# M228A.net
KiCad netlist of a schematic drawn in EAGLE
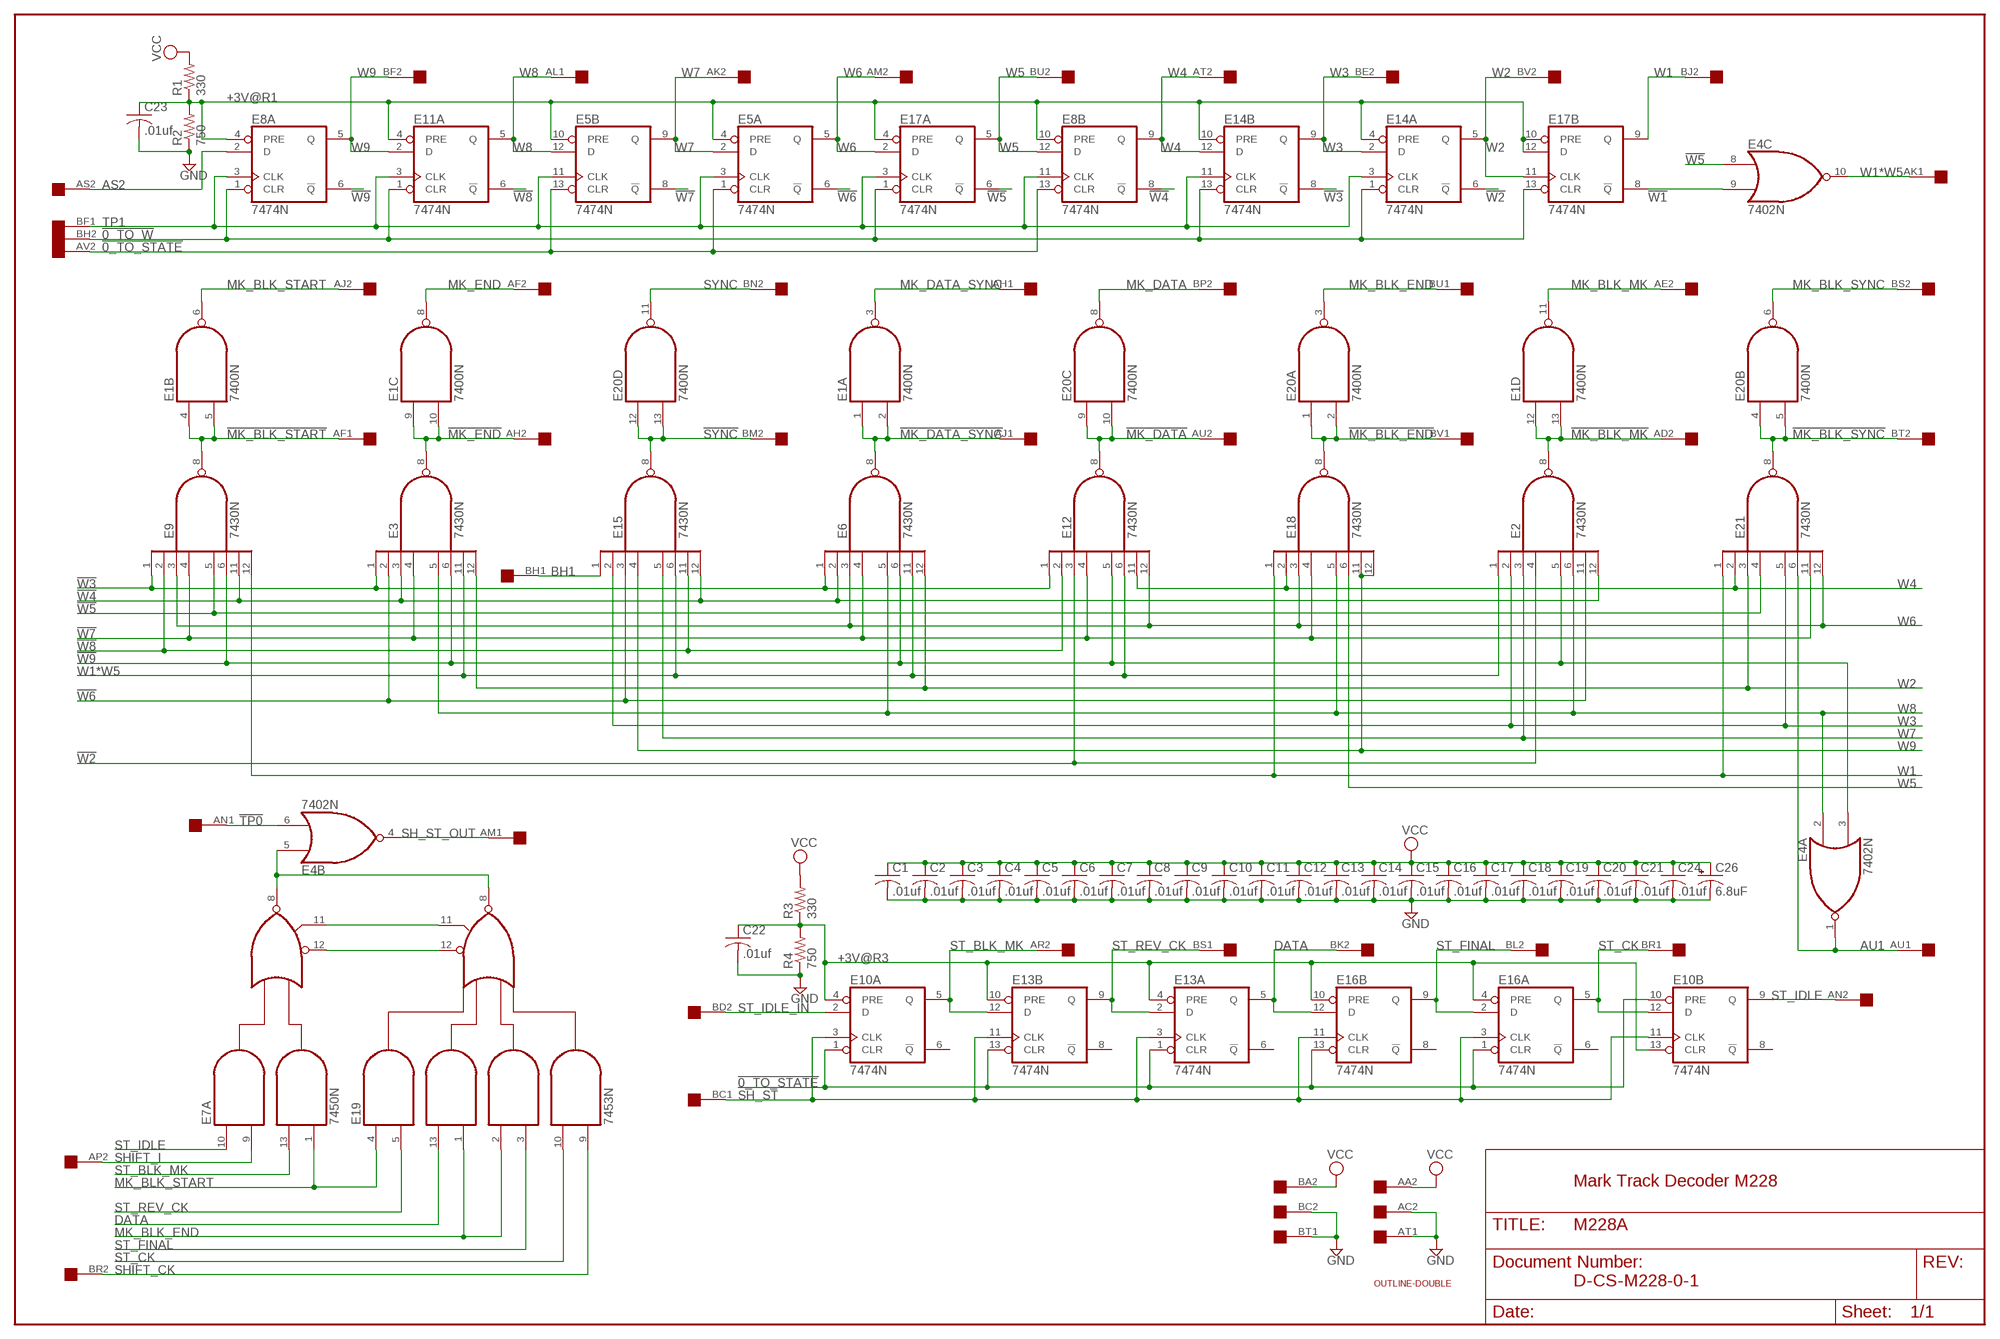
[diagram p0: schematic, sheet 1]

(export (version "E")
  (design (tool "Eeschema 10.0.6"))
  (components
    (comp (ref "C1")
      (value ".01uf")
      (footprint "eagle-import:C050-025X075")
      (libsource (lib "eagle-import") (part "C-US050-025X075"))
    )
    (comp (ref "C2")
      (value ".01uf")
      (footprint "eagle-import:C050-025X075")
      (libsource (lib "eagle-import") (part "C-US050-025X075"))
    )
    (comp (ref "C3")
      (value ".01uf")
      (footprint "eagle-import:C050-025X075")
      (libsource (lib "eagle-import") (part "C-US050-025X075"))
    )
    (comp (ref "C4")
      (value ".01uf")
      (footprint "eagle-import:C050-025X075")
      (libsource (lib "eagle-import") (part "C-US050-025X075"))
    )
    (comp (ref "C5")
      (value ".01uf")
      (footprint "eagle-import:C050-025X075")
      (libsource (lib "eagle-import") (part "C-US050-025X075"))
    )
    (comp (ref "C6")
      (value ".01uf")
      (footprint "eagle-import:C050-025X075")
      (libsource (lib "eagle-import") (part "C-US050-025X075"))
    )
    (comp (ref "C7")
      (value ".01uf")
      (footprint "eagle-import:C050-025X075")
      (libsource (lib "eagle-import") (part "C-US050-025X075"))
    )
    (comp (ref "C8")
      (value ".01uf")
      (footprint "eagle-import:C050-025X075")
      (libsource (lib "eagle-import") (part "C-US050-025X075"))
    )
    (comp (ref "C9")
      (value ".01uf")
      (footprint "eagle-import:C050-025X075")
      (libsource (lib "eagle-import") (part "C-US050-025X075"))
    )
    (comp (ref "C10")
      (value ".01uf")
      (footprint "eagle-import:C050-025X075")
      (libsource (lib "eagle-import") (part "C-US050-025X075"))
    )
    (comp (ref "C11")
      (value ".01uf")
      (footprint "eagle-import:C050-025X075")
      (libsource (lib "eagle-import") (part "C-US050-025X075"))
    )
    (comp (ref "C12")
      (value ".01uf")
      (footprint "eagle-import:C050-025X075")
      (libsource (lib "eagle-import") (part "C-US050-025X075"))
    )
    (comp (ref "C13")
      (value ".01uf")
      (footprint "eagle-import:C050-025X075")
      (libsource (lib "eagle-import") (part "C-US050-025X075"))
    )
    (comp (ref "C14")
      (value ".01uf")
      (footprint "eagle-import:C050-025X075")
      (libsource (lib "eagle-import") (part "C-US050-025X075"))
    )
    (comp (ref "C15")
      (value ".01uf")
      (footprint "eagle-import:C050-025X075")
      (libsource (lib "eagle-import") (part "C-US050-025X075"))
    )
    (comp (ref "C16")
      (value ".01uf")
      (footprint "eagle-import:C050-025X075")
      (libsource (lib "eagle-import") (part "C-US050-025X075"))
    )
    (comp (ref "C17")
      (value ".01uf")
      (footprint "eagle-import:C050-025X075")
      (libsource (lib "eagle-import") (part "C-US050-025X075"))
    )
    (comp (ref "C18")
      (value ".01uf")
      (footprint "eagle-import:C050-025X075")
      (libsource (lib "eagle-import") (part "C-US050-025X075"))
    )
    (comp (ref "C19")
      (value ".01uf")
      (footprint "eagle-import:C050-025X075")
      (libsource (lib "eagle-import") (part "C-US050-025X075"))
    )
    (comp (ref "C20")
      (value ".01uf")
      (footprint "eagle-import:C050-025X075")
      (libsource (lib "eagle-import") (part "C-US050-025X075"))
    )
    (comp (ref "C21")
      (value ".01uf")
      (footprint "eagle-import:C050-025X075")
      (libsource (lib "eagle-import") (part "C-US050-025X075"))
    )
    (comp (ref "C22")
      (value ".01uf")
      (footprint "eagle-import:C050-025X075")
      (libsource (lib "eagle-import") (part "C-US050-025X075"))
    )
    (comp (ref "C23")
      (value ".01uf")
      (footprint "eagle-import:C050-025X075")
      (libsource (lib "eagle-import") (part "C-US050-025X075"))
    )
    (comp (ref "C24")
      (value ".01uf")
      (footprint "eagle-import:C050-025X075")
      (libsource (lib "eagle-import") (part "C-US050-025X075"))
    )
    (comp (ref "C26")
      (value "6.8uF")
      (footprint "eagle-import:E22-6")
      (libsource (lib "eagle-import") (part "CPOL-USE22-6AXIAL"))
    )
    (comp (ref "E1")
      (value "7400N")
      (footprint "eagle-import:DIL14")
      (libsource (lib "eagle-import") (part "7400N"))
    )
    (comp (ref "E2")
      (value "7430N")
      (footprint "eagle-import:DIL14")
      (libsource (lib "eagle-import") (part "7430N"))
    )
    (comp (ref "E3")
      (value "7430N")
      (footprint "eagle-import:DIL14")
      (libsource (lib "eagle-import") (part "7430N"))
    )
    (comp (ref "E4")
      (value "7402N")
      (footprint "eagle-import:DIL14")
      (libsource (lib "eagle-import") (part "7402N"))
    )
    (comp (ref "E5")
      (value "7474N")
      (footprint "eagle-import:DIL14")
      (libsource (lib "eagle-import") (part "7474NS"))
    )
    (comp (ref "E6")
      (value "7430N")
      (footprint "eagle-import:DIL14")
      (libsource (lib "eagle-import") (part "7430N"))
    )
    (comp (ref "E7")
      (value "7450N")
      (footprint "eagle-import:DIL14")
      (libsource (lib "eagle-import") (part "7450N"))
    )
    (comp (ref "E8")
      (value "7474N")
      (footprint "eagle-import:DIL14")
      (libsource (lib "eagle-import") (part "7474NS"))
    )
    (comp (ref "E9")
      (value "7430N")
      (footprint "eagle-import:DIL14")
      (libsource (lib "eagle-import") (part "7430N"))
    )
    (comp (ref "E10")
      (value "7474N")
      (footprint "eagle-import:DIL14")
      (libsource (lib "eagle-import") (part "7474NS"))
    )
    (comp (ref "E11")
      (value "7474N")
      (footprint "eagle-import:DIL14")
      (libsource (lib "eagle-import") (part "7474NS"))
    )
    (comp (ref "E12")
      (value "7430N")
      (footprint "eagle-import:DIL14")
      (libsource (lib "eagle-import") (part "7430N"))
    )
    (comp (ref "E13")
      (value "7474N")
      (footprint "eagle-import:DIL14")
      (libsource (lib "eagle-import") (part "7474NS"))
    )
    (comp (ref "E14")
      (value "7474N")
      (footprint "eagle-import:DIL14")
      (libsource (lib "eagle-import") (part "7474NS"))
    )
    (comp (ref "E15")
      (value "7430N")
      (footprint "eagle-import:DIL14")
      (libsource (lib "eagle-import") (part "7430N"))
    )
    (comp (ref "E16")
      (value "7474N")
      (footprint "eagle-import:DIL14")
      (libsource (lib "eagle-import") (part "7474NS"))
    )
    (comp (ref "E17")
      (value "7474N")
      (footprint "eagle-import:DIL14")
      (libsource (lib "eagle-import") (part "7474NS"))
    )
    (comp (ref "E18")
      (value "7430N")
      (footprint "eagle-import:DIL14")
      (libsource (lib "eagle-import") (part "7430N"))
    )
    (comp (ref "E19")
      (value "7453N")
      (footprint "eagle-import:DIL14")
      (libsource (lib "eagle-import") (part "7453N"))
    )
    (comp (ref "E20")
      (value "7400N")
      (footprint "eagle-import:DIL14")
      (libsource (lib "eagle-import") (part "7400N"))
    )
    (comp (ref "E21")
      (value "7430N")
      (footprint "eagle-import:DIL14")
      (libsource (lib "eagle-import") (part "7430N"))
    )
    (comp (ref "R1")
      (value "330")
      (footprint "eagle-import:0207_10")
      (libsource (lib "eagle-import") (part "R-US_0207/10"))
    )
    (comp (ref "R2")
      (value "750")
      (footprint "eagle-import:0207_10")
      (libsource (lib "eagle-import") (part "R-US_0207/10"))
    )
    (comp (ref "R3")
      (value "330")
      (footprint "eagle-import:0207_10")
      (libsource (lib "eagle-import") (part "R-US_0207/10"))
    )
    (comp (ref "R4")
      (value "750")
      (footprint "eagle-import:0207_10")
      (libsource (lib "eagle-import") (part "R-US_0207/10"))
    )
    (comp (ref "U$1")
      (value "OUTLINE-DOUBLE")
      (footprint "eagle-import:DOUBLE")
      (libsource (lib "eagle-import") (part "OUTLINE-DOUBLE"))
    )
    (comp (ref "U$5")
      (value "DOUBLE")
      (footprint "eagle-import:EDGE-CON4")
      (libsource (lib "eagle-import") (part "DOUBLE"))
    )
  )
  (nets
    (net (code "1") (name "/+3V@R1") (class "Default")
      (node (ref "C23") (pin "1") (pinfunction "1_1") (pintype "passive"))
      (node (ref "E11") (pin "4") (pinfunction "PRE_4") (pintype "input"))
      (node (ref "E14") (pin "10") (pinfunction "PRE_10") (pintype "input"))
      (node (ref "E14") (pin "4") (pinfunction "PRE_4") (pintype "input"))
      (node (ref "E17") (pin "10") (pinfunction "PRE_10") (pintype "input"))
      (node (ref "E17") (pin "12") (pinfunction "D_12") (pintype "input"))
      (node (ref "E17") (pin "4") (pinfunction "PRE_4") (pintype "input"))
      (node (ref "E5") (pin "10") (pinfunction "PRE_10") (pintype "input"))
      (node (ref "E5") (pin "4") (pinfunction "PRE_4") (pintype "input"))
      (node (ref "E8") (pin "10") (pinfunction "PRE_10") (pintype "input"))
      (node (ref "E8") (pin "4") (pinfunction "PRE_4") (pintype "input"))
      (node (ref "R1") (pin "1") (pinfunction "1_1") (pintype "passive"))
      (node (ref "R2") (pin "2") (pinfunction "2_2") (pintype "passive"))
    )
    (net (code "2") (name "/+3V@R3") (class "Default")
      (node (ref "C22") (pin "1") (pinfunction "1_1") (pintype "passive"))
      (node (ref "E10") (pin "13") (pinfunction "CLR_13") (pintype "input"))
      (node (ref "E10") (pin "4") (pinfunction "PRE_4") (pintype "input"))
      (node (ref "E13") (pin "10") (pinfunction "PRE_10") (pintype "input"))
      (node (ref "E13") (pin "4") (pinfunction "PRE_4") (pintype "input"))
      (node (ref "E16") (pin "10") (pinfunction "PRE_10") (pintype "input"))
      (node (ref "E16") (pin "4") (pinfunction "PRE_4") (pintype "input"))
      (node (ref "R3") (pin "1") (pinfunction "1_1") (pintype "passive"))
      (node (ref "R4") (pin "2") (pinfunction "2_2") (pintype "passive"))
    )
    (net (code "3") (name "/AS2") (class "Default")
      (node (ref "E8") (pin "2") (pinfunction "D_2") (pintype "input"))
      (node (ref "U$5") (pin "AS2") (pinfunction "1_AS2") (pintype "bidirectional"))
    )
    (net (code "4") (name "/AU1") (class "Default")
      (node (ref "E21") (pin "6") (pinfunction "I5_6") (pintype "input"))
      (node (ref "E4") (pin "1") (pinfunction "O_1") (pintype "output"))
      (node (ref "U$5") (pin "AU1") (pinfunction "1_AU1") (pintype "bidirectional"))
    )
    (net (code "5") (name "/BH1") (class "Default")
      (node (ref "E15") (pin "1") (pinfunction "I0_1") (pintype "input"))
      (node (ref "U$5") (pin "BH1") (pinfunction "1_BH1") (pintype "bidirectional"))
    )
    (net (code "6") (name "/DATA") (class "Default")
      (node (ref "E13") (pin "5") (pinfunction "Q_5") (pintype "output"))
      (node (ref "E16") (pin "12") (pinfunction "D_12") (pintype "input"))
      (node (ref "E19") (pin "13") (pinfunction "I3_13") (pintype "input"))
      (node (ref "U$5") (pin "BK2") (pinfunction "1_BK2") (pintype "bidirectional"))
    )
    (net (code "7") (name "/MK_BLK_END") (class "Default")
      (node (ref "E19") (pin "1") (pinfunction "I4_1") (pintype "input"))
      (node (ref "E19") (pin "2") (pinfunction "I5_2") (pintype "input"))
      (node (ref "E20") (pin "3") (pinfunction "O_3") (pintype "output"))
      (node (ref "U$5") (pin "BU1") (pinfunction "1_BU1") (pintype "bidirectional"))
    )
    (net (code "8") (name "/MK_BLK_MK") (class "Default")
      (node (ref "E1") (pin "11") (pinfunction "O_11") (pintype "output"))
      (node (ref "U$5") (pin "AE2") (pinfunction "1_AE2") (pintype "bidirectional"))
    )
    (net (code "9") (name "/MK_BLK_START") (class "Default")
      (node (ref "E1") (pin "6") (pinfunction "O_6") (pintype "output"))
      (node (ref "E19") (pin "4") (pinfunction "I1_4") (pintype "input"))
      (node (ref "E7") (pin "1") (pinfunction "I4_1") (pintype "input"))
      (node (ref "U$5") (pin "AJ2") (pinfunction "1_AJ2") (pintype "bidirectional"))
    )
    (net (code "10") (name "/MK_BLK_SYNC") (class "Default")
      (node (ref "E20") (pin "6") (pinfunction "O_6") (pintype "output"))
      (node (ref "U$5") (pin "BS2") (pinfunction "1_BS2") (pintype "bidirectional"))
    )
    (net (code "11") (name "/MK_DATA") (class "Default")
      (node (ref "E20") (pin "8") (pinfunction "O_8") (pintype "output"))
      (node (ref "U$5") (pin "BP2") (pinfunction "1_BP2") (pintype "bidirectional"))
    )
    (net (code "12") (name "/MK_DATA_SYNC") (class "Default")
      (node (ref "E1") (pin "3") (pinfunction "O_3") (pintype "output"))
      (node (ref "U$5") (pin "AH1") (pinfunction "1_AH1") (pintype "bidirectional"))
    )
    (net (code "13") (name "/MK_END") (class "Default")
      (node (ref "E1") (pin "8") (pinfunction "O_8") (pintype "output"))
      (node (ref "U$5") (pin "AF2") (pinfunction "1_AF2") (pintype "bidirectional"))
    )
    (net (code "14") (name "/SHIFT_CK") (class "Default")
      (node (ref "E19") (pin "9") (pinfunction "I8_9") (pintype "input"))
      (node (ref "U$5") (pin "BR2") (pinfunction "1_BR2") (pintype "bidirectional"))
    )
    (net (code "15") (name "/SHIFT_I") (class "Default")
      (node (ref "E7") (pin "9") (pinfunction "I2_9") (pintype "input"))
      (node (ref "U$5") (pin "AP2") (pinfunction "1_AP2") (pintype "bidirectional"))
    )
    (net (code "16") (name "/SH_ST") (class "Default")
      (node (ref "E10") (pin "11") (pinfunction "CLK_11") (pintype "input"))
      (node (ref "E10") (pin "3") (pinfunction "CLK_3") (pintype "input"))
      (node (ref "E13") (pin "11") (pinfunction "CLK_11") (pintype "input"))
      (node (ref "E13") (pin "3") (pinfunction "CLK_3") (pintype "input"))
      (node (ref "E16") (pin "11") (pinfunction "CLK_11") (pintype "input"))
      (node (ref "E16") (pin "3") (pinfunction "CLK_3") (pintype "input"))
      (node (ref "U$5") (pin "BC1") (pinfunction "1_BC1") (pintype "bidirectional"))
    )
    (net (code "17") (name "/SH_ST_OUT") (class "Default")
      (node (ref "E4") (pin "4") (pinfunction "O_4") (pintype "output"))
      (node (ref "U$5") (pin "AM1") (pinfunction "1_AM1") (pintype "bidirectional"))
    )
    (net (code "18") (name "/ST_BLK_MK") (class "Default")
      (node (ref "E10") (pin "5") (pinfunction "Q_5") (pintype "output"))
      (node (ref "E13") (pin "12") (pinfunction "D_12") (pintype "input"))
      (node (ref "E7") (pin "13") (pinfunction "I3_13") (pintype "input"))
      (node (ref "U$5") (pin "AR2") (pinfunction "1_AR2") (pintype "bidirectional"))
    )
    (net (code "19") (name "/ST_CK") (class "Default")
      (node (ref "E10") (pin "12") (pinfunction "D_12") (pintype "input"))
      (node (ref "E16") (pin "5") (pinfunction "Q_5") (pintype "output"))
      (node (ref "E19") (pin "10") (pinfunction "I7_10") (pintype "input"))
      (node (ref "U$5") (pin "BR1") (pinfunction "1_BR1") (pintype "bidirectional"))
    )
    (net (code "20") (name "/ST_FINAL") (class "Default")
      (node (ref "E16") (pin "2") (pinfunction "D_2") (pintype "input"))
      (node (ref "E16") (pin "9") (pinfunction "Q_9") (pintype "output"))
      (node (ref "E19") (pin "3") (pinfunction "I6_3") (pintype "input"))
      (node (ref "U$5") (pin "BL2") (pinfunction "1_BL2") (pintype "bidirectional"))
    )
    (net (code "21") (name "/ST_IDLE") (class "Default")
      (node (ref "E10") (pin "9") (pinfunction "Q_9") (pintype "output"))
      (node (ref "E7") (pin "10") (pinfunction "I1_10") (pintype "input"))
      (node (ref "U$5") (pin "AN2") (pinfunction "1_AN2") (pintype "bidirectional"))
    )
    (net (code "22") (name "/ST_IDLE_IN") (class "Default")
      (node (ref "E10") (pin "2") (pinfunction "D_2") (pintype "input"))
      (node (ref "U$5") (pin "BD2") (pinfunction "1_BD2") (pintype "bidirectional"))
    )
    (net (code "23") (name "/ST_REV_CK") (class "Default")
      (node (ref "E13") (pin "2") (pinfunction "D_2") (pintype "input"))
      (node (ref "E13") (pin "9") (pinfunction "Q_9") (pintype "output"))
      (node (ref "E19") (pin "5") (pinfunction "I2_5") (pintype "input"))
      (node (ref "U$5") (pin "BS1") (pinfunction "1_BS1") (pintype "bidirectional"))
    )
    (net (code "24") (name "/SYNC") (class "Default")
      (node (ref "E20") (pin "11") (pinfunction "O_11") (pintype "output"))
      (node (ref "U$5") (pin "BN2") (pinfunction "1_BN2") (pintype "bidirectional"))
    )
    (net (code "25") (name "/TP1") (class "Default")
      (node (ref "E11") (pin "3") (pinfunction "CLK_3") (pintype "input"))
      (node (ref "E14") (pin "11") (pinfunction "CLK_11") (pintype "input"))
      (node (ref "E14") (pin "3") (pinfunction "CLK_3") (pintype "input"))
      (node (ref "E17") (pin "3") (pinfunction "CLK_3") (pintype "input"))
      (node (ref "E5") (pin "11") (pinfunction "CLK_11") (pintype "input"))
      (node (ref "E5") (pin "3") (pinfunction "CLK_3") (pintype "input"))
      (node (ref "E8") (pin "11") (pinfunction "CLK_11") (pintype "input"))
      (node (ref "E8") (pin "3") (pinfunction "CLK_3") (pintype "input"))
      (node (ref "U$5") (pin "BF1") (pinfunction "1_BF1") (pintype "bidirectional"))
    )
    (net (code "26") (name "/W1") (class "Default")
      (node (ref "E17") (pin "9") (pinfunction "Q_9") (pintype "output"))
      (node (ref "E18") (pin "1") (pinfunction "I0_1") (pintype "input"))
      (node (ref "E21") (pin "1") (pinfunction "I0_1") (pintype "input"))
      (node (ref "E9") (pin "12") (pinfunction "I7_12") (pintype "input"))
      (node (ref "U$5") (pin "BJ2") (pinfunction "1_BJ2") (pintype "bidirectional"))
    )
    (net (code "27") (name "/W1*W5") (class "Default")
      (node (ref "E12") (pin "6") (pinfunction "I5_6") (pintype "input"))
      (node (ref "E15") (pin "6") (pinfunction "I5_6") (pintype "input"))
      (node (ref "E2") (pin "1") (pinfunction "I0_1") (pintype "input"))
      (node (ref "E3") (pin "11") (pinfunction "I6_11") (pintype "input"))
      (node (ref "E4") (pin "10") (pinfunction "O_10") (pintype "output"))
      (node (ref "E6") (pin "11") (pinfunction "I6_11") (pintype "input"))
      (node (ref "U$5") (pin "AK1") (pinfunction "1_AK1") (pintype "bidirectional"))
    )
    (net (code "28") (name "/W2") (class "Default")
      (node (ref "E14") (pin "5") (pinfunction "Q_5") (pintype "output"))
      (node (ref "E17") (pin "11") (pinfunction "CLK_11") (pintype "input"))
      (node (ref "E21") (pin "3") (pinfunction "I2_3") (pintype "input"))
      (node (ref "E3") (pin "12") (pinfunction "I7_12") (pintype "input"))
      (node (ref "E6") (pin "12") (pinfunction "I7_12") (pintype "input"))
      (node (ref "U$5") (pin "BV2") (pinfunction "1_BV2") (pintype "bidirectional"))
    )
    (net (code "29") (name "/W3") (class "Default")
      (node (ref "E14") (pin "2") (pinfunction "D_2") (pintype "input"))
      (node (ref "E14") (pin "9") (pinfunction "Q_9") (pintype "output"))
      (node (ref "E15") (pin "2") (pinfunction "I1_2") (pintype "input"))
      (node (ref "E2") (pin "2") (pinfunction "I1_2") (pintype "input"))
      (node (ref "E21") (pin "5") (pinfunction "I4_5") (pintype "input"))
      (node (ref "U$5") (pin "BE2") (pinfunction "1_BE2") (pintype "bidirectional"))
    )
    (net (code "30") (name "/W4") (class "Default")
      (node (ref "E12") (pin "11") (pinfunction "I6_11") (pintype "input"))
      (node (ref "E14") (pin "12") (pinfunction "D_12") (pintype "input"))
      (node (ref "E18") (pin "2") (pinfunction "I1_2") (pintype "input"))
      (node (ref "E21") (pin "2") (pinfunction "I1_2") (pintype "input"))
      (node (ref "E8") (pin "9") (pinfunction "Q_9") (pintype "output"))
      (node (ref "U$5") (pin "AT2") (pinfunction "1_AT2") (pintype "bidirectional"))
    )
    (net (code "31") (name "/W5") (class "Default")
      (node (ref "E17") (pin "5") (pinfunction "Q_5") (pintype "output"))
      (node (ref "E18") (pin "6") (pinfunction "I5_6") (pintype "input"))
      (node (ref "E8") (pin "12") (pinfunction "D_12") (pintype "input"))
      (node (ref "U$5") (pin "BU2") (pinfunction "1_BU2") (pintype "bidirectional"))
    )
    (net (code "32") (name "/W6") (class "Default")
      (node (ref "E12") (pin "12") (pinfunction "I7_12") (pintype "input"))
      (node (ref "E17") (pin "2") (pinfunction "D_2") (pintype "input"))
      (node (ref "E18") (pin "3") (pinfunction "I2_3") (pintype "input"))
      (node (ref "E21") (pin "12") (pinfunction "I7_12") (pintype "input"))
      (node (ref "E5") (pin "5") (pinfunction "Q_5") (pintype "output"))
      (node (ref "E6") (pin "3") (pinfunction "I2_3") (pintype "input"))
      (node (ref "E9") (pin "3") (pinfunction "I2_3") (pintype "input"))
      (node (ref "U$5") (pin "AM2") (pinfunction "1_AM2") (pintype "bidirectional"))
    )
    (net (code "33") (name "/W7") (class "Default")
      (node (ref "E15") (pin "5") (pinfunction "I4_5") (pintype "input"))
      (node (ref "E2") (pin "3") (pinfunction "I2_3") (pintype "input"))
      (node (ref "E5") (pin "2") (pinfunction "D_2") (pintype "input"))
      (node (ref "E5") (pin "9") (pinfunction "Q_9") (pintype "output"))
      (node (ref "U$5") (pin "AK2") (pinfunction "1_AK2") (pintype "bidirectional"))
    )
    (net (code "34") (name "/W8") (class "Default")
      (node (ref "E11") (pin "5") (pinfunction "Q_5") (pintype "output"))
      (node (ref "E18") (pin "5") (pinfunction "I4_5") (pintype "input"))
      (node (ref "E2") (pin "6") (pinfunction "I5_6") (pintype "input"))
      (node (ref "E3") (pin "5") (pinfunction "I4_5") (pintype "input"))
      (node (ref "E4") (pin "2") (pinfunction "I0_2") (pintype "input"))
      (node (ref "E5") (pin "12") (pinfunction "D_12") (pintype "input"))
      (node (ref "E6") (pin "5") (pinfunction "I4_5") (pintype "input"))
      (node (ref "U$5") (pin "AL1") (pinfunction "1_AL1") (pintype "bidirectional"))
    )
    (net (code "35") (name "/W9") (class "Default")
      (node (ref "E11") (pin "2") (pinfunction "D_2") (pintype "input"))
      (node (ref "E15") (pin "4") (pinfunction "I3_4") (pintype "input"))
      (node (ref "E18") (pin "11") (pinfunction "I6_11") (pintype "input"))
      (node (ref "E18") (pin "12") (pinfunction "I7_12") (pintype "input"))
      (node (ref "E8") (pin "5") (pinfunction "Q_5") (pintype "output"))
      (node (ref "U$5") (pin "BF2") (pinfunction "1_BF2") (pintype "bidirectional"))
    )
    (net (code "36") (name "/~{0_TO_STATE}") (class "Default")
      (node (ref "E10") (pin "1") (pinfunction "CLR_1") (pintype "input"))
      (node (ref "E10") (pin "10") (pinfunction "PRE_10") (pintype "input"))
      (node (ref "E13") (pin "1") (pinfunction "CLR_1") (pintype "input"))
      (node (ref "E13") (pin "13") (pinfunction "CLR_13") (pintype "input"))
      (node (ref "E16") (pin "1") (pinfunction "CLR_1") (pintype "input"))
      (node (ref "E16") (pin "13") (pinfunction "CLR_13") (pintype "input"))
      (node (ref "E5") (pin "1") (pinfunction "CLR_1") (pintype "input"))
      (node (ref "E5") (pin "13") (pinfunction "CLR_13") (pintype "input"))
      (node (ref "E8") (pin "13") (pinfunction "CLR_13") (pintype "input"))
      (node (ref "U$5") (pin "AV2") (pinfunction "1_AV2") (pintype "bidirectional"))
    )
    (net (code "37") (name "/~{0_TO_W}") (class "Default")
      (node (ref "E11") (pin "1") (pinfunction "CLR_1") (pintype "input"))
      (node (ref "E14") (pin "1") (pinfunction "CLR_1") (pintype "input"))
      (node (ref "E14") (pin "13") (pinfunction "CLR_13") (pintype "input"))
      (node (ref "E17") (pin "1") (pinfunction "CLR_1") (pintype "input"))
      (node (ref "E17") (pin "13") (pinfunction "CLR_13") (pintype "input"))
      (node (ref "E8") (pin "1") (pinfunction "CLR_1") (pintype "input"))
      (node (ref "U$5") (pin "BH2") (pinfunction "1_BH2") (pintype "bidirectional"))
    )
    (net (code "38") (name "/~{MK_BLK_END}") (class "Default")
      (node (ref "E18") (pin "8") (pinfunction "O_8") (pintype "output"))
      (node (ref "E20") (pin "1") (pinfunction "I0_1") (pintype "input"))
      (node (ref "E20") (pin "2") (pinfunction "I1_2") (pintype "input"))
      (node (ref "U$5") (pin "BV1") (pinfunction "1_BV1") (pintype "bidirectional"))
    )
    (net (code "39") (name "/~{MK_BLK_MK}") (class "Default")
      (node (ref "E1") (pin "12") (pinfunction "I0_12") (pintype "input"))
      (node (ref "E1") (pin "13") (pinfunction "I1_13") (pintype "input"))
      (node (ref "E2") (pin "8") (pinfunction "O_8") (pintype "output"))
      (node (ref "U$5") (pin "AD2") (pinfunction "1_AD2") (pintype "bidirectional"))
    )
    (net (code "40") (name "/~{MK_BLK_START}") (class "Default")
      (node (ref "E1") (pin "4") (pinfunction "I0_4") (pintype "input"))
      (node (ref "E1") (pin "5") (pinfunction "I1_5") (pintype "input"))
      (node (ref "E9") (pin "8") (pinfunction "O_8") (pintype "output"))
      (node (ref "U$5") (pin "AF1") (pinfunction "1_AF1") (pintype "bidirectional"))
    )
    (net (code "41") (name "/~{MK_BLK_SYNC}") (class "Default")
      (node (ref "E20") (pin "4") (pinfunction "I0_4") (pintype "input"))
      (node (ref "E20") (pin "5") (pinfunction "I1_5") (pintype "input"))
      (node (ref "E21") (pin "8") (pinfunction "O_8") (pintype "output"))
      (node (ref "U$5") (pin "BT2") (pinfunction "1_BT2") (pintype "bidirectional"))
    )
    (net (code "42") (name "/~{MK_DATA_SYNC}") (class "Default")
      (node (ref "E1") (pin "1") (pinfunction "I0_1") (pintype "input"))
      (node (ref "E1") (pin "2") (pinfunction "I1_2") (pintype "input"))
      (node (ref "E6") (pin "8") (pinfunction "O_8") (pintype "output"))
      (node (ref "U$5") (pin "AJ1") (pinfunction "1_AJ1") (pintype "bidirectional"))
    )
    (net (code "43") (name "/~{MK_DATA}") (class "Default")
      (node (ref "E12") (pin "8") (pinfunction "O_8") (pintype "output"))
      (node (ref "E20") (pin "10") (pinfunction "I1_10") (pintype "input"))
      (node (ref "E20") (pin "9") (pinfunction "I0_9") (pintype "input"))
      (node (ref "U$5") (pin "AU2") (pinfunction "1_AU2") (pintype "bidirectional"))
    )
    (net (code "44") (name "/~{MK_END}") (class "Default")
      (node (ref "E1") (pin "10") (pinfunction "I1_10") (pintype "input"))
      (node (ref "E1") (pin "9") (pinfunction "I0_9") (pintype "input"))
      (node (ref "E3") (pin "8") (pinfunction "O_8") (pintype "output"))
      (node (ref "U$5") (pin "AH2") (pinfunction "1_AH2") (pintype "bidirectional"))
    )
    (net (code "45") (name "/~{SYNC}") (class "Default")
      (node (ref "E15") (pin "8") (pinfunction "O_8") (pintype "output"))
      (node (ref "E20") (pin "12") (pinfunction "I0_12") (pintype "input"))
      (node (ref "E20") (pin "13") (pinfunction "I1_13") (pintype "input"))
      (node (ref "U$5") (pin "BM2") (pinfunction "1_BM2") (pintype "bidirectional"))
    )
    (net (code "46") (name "/~{TP0}") (class "Default")
      (node (ref "E4") (pin "6") (pinfunction "I1_6") (pintype "input"))
      (node (ref "U$5") (pin "AN1") (pinfunction "1_AN1") (pintype "bidirectional"))
    )
    (net (code "47") (name "/~{W1}") (class "Default")
      (node (ref "E17") (pin "8") (pinfunction "~{Q}_8") (pintype "output"))
      (node (ref "E4") (pin "9") (pinfunction "I1_9") (pintype "input"))
    )
    (net (code "48") (name "/~{W2}") (class "Default")
      (node (ref "E12") (pin "3") (pinfunction "I2_3") (pintype "input"))
      (node (ref "E14") (pin "6") (pinfunction "~{Q}_6") (pintype "output"))
      (node (ref "E2") (pin "4") (pinfunction "I3_4") (pintype "input"))
    )
    (net (code "49") (name "/~{W3}") (class "Default")
      (node (ref "E12") (pin "1") (pinfunction "I0_1") (pintype "input"))
      (node (ref "E14") (pin "8") (pinfunction "~{Q}_8") (pintype "output"))
      (node (ref "E3") (pin "1") (pinfunction "I0_1") (pintype "input"))
      (node (ref "E6") (pin "1") (pinfunction "I0_1") (pintype "input"))
      (node (ref "E9") (pin "1") (pinfunction "I0_1") (pintype "input"))
    )
    (net (code "50") (name "/~{W4}") (class "Default")
      (node (ref "E15") (pin "12") (pinfunction "I7_12") (pintype "input"))
      (node (ref "E2") (pin "12") (pinfunction "I7_12") (pintype "input"))
      (node (ref "E3") (pin "3") (pinfunction "I2_3") (pintype "input"))
      (node (ref "E6") (pin "2") (pinfunction "I1_2") (pintype "input"))
      (node (ref "E8") (pin "8") (pinfunction "~{Q}_8") (pintype "output"))
      (node (ref "E9") (pin "11") (pinfunction "I6_11") (pintype "input"))
    )
    (net (code "51") (name "/~{W5}") (class "Default")
      (node (ref "E17") (pin "6") (pinfunction "~{Q}_6") (pintype "output"))
      (node (ref "E21") (pin "4") (pinfunction "I3_4") (pintype "input"))
      (node (ref "E4") (pin "8") (pinfunction "I0_8") (pintype "input"))
      (node (ref "E9") (pin "5") (pinfunction "I4_5") (pintype "input"))
    )
    (net (code "52") (name "/~{W6}") (class "Default")
      (node (ref "E15") (pin "3") (pinfunction "I2_3") (pintype "input"))
      (node (ref "E2") (pin "11") (pinfunction "I6_11") (pintype "input"))
      (node (ref "E3") (pin "2") (pinfunction "I1_2") (pintype "input"))
      (node (ref "E5") (pin "6") (pinfunction "~{Q}_6") (pintype "output"))
    )
    (net (code "53") (name "/~{W7}") (class "Default")
      (node (ref "E12") (pin "4") (pinfunction "I3_4") (pintype "input"))
      (node (ref "E18") (pin "4") (pinfunction "I3_4") (pintype "input"))
      (node (ref "E21") (pin "11") (pinfunction "I6_11") (pintype "input"))
      (node (ref "E3") (pin "4") (pinfunction "I3_4") (pintype "input"))
      (node (ref "E5") (pin "8") (pinfunction "~{Q}_8") (pintype "output"))
      (node (ref "E6") (pin "4") (pinfunction "I3_4") (pintype "input"))
      (node (ref "E9") (pin "4") (pinfunction "I3_4") (pintype "input"))
    )
    (net (code "54") (name "/~{W8}") (class "Default")
      (node (ref "E11") (pin "6") (pinfunction "~{Q}_6") (pintype "output"))
      (node (ref "E12") (pin "2") (pinfunction "I1_2") (pintype "input"))
      (node (ref "E15") (pin "11") (pinfunction "I6_11") (pintype "input"))
      (node (ref "E9") (pin "2") (pinfunction "I1_2") (pintype "input"))
    )
    (net (code "55") (name "/~{W9}") (class "Default")
      (node (ref "E12") (pin "5") (pinfunction "I4_5") (pintype "input"))
      (node (ref "E2") (pin "5") (pinfunction "I4_5") (pintype "input"))
      (node (ref "E3") (pin "6") (pinfunction "I5_6") (pintype "input"))
      (node (ref "E4") (pin "3") (pinfunction "I1_3") (pintype "input"))
      (node (ref "E6") (pin "6") (pinfunction "I5_6") (pintype "input"))
      (node (ref "E8") (pin "6") (pinfunction "~{Q}_6") (pintype "output"))
      (node (ref "E9") (pin "6") (pinfunction "I5_6") (pintype "input"))
    )
    (net (code "56") (name "GND") (class "Default")
      (node (ref "C1") (pin "2") (pinfunction "2_2") (pintype "passive"))
      (node (ref "C10") (pin "2") (pinfunction "2_2") (pintype "passive"))
      (node (ref "C11") (pin "2") (pinfunction "2_2") (pintype "passive"))
      (node (ref "C12") (pin "2") (pinfunction "2_2") (pintype "passive"))
      (node (ref "C13") (pin "2") (pinfunction "2_2") (pintype "passive"))
      (node (ref "C14") (pin "2") (pinfunction "2_2") (pintype "passive"))
      (node (ref "C15") (pin "2") (pinfunction "2_2") (pintype "passive"))
      (node (ref "C16") (pin "2") (pinfunction "2_2") (pintype "passive"))
      (node (ref "C17") (pin "2") (pinfunction "2_2") (pintype "passive"))
      (node (ref "C18") (pin "2") (pinfunction "2_2") (pintype "passive"))
      (node (ref "C19") (pin "2") (pinfunction "2_2") (pintype "passive"))
      (node (ref "C2") (pin "2") (pinfunction "2_2") (pintype "passive"))
      (node (ref "C20") (pin "2") (pinfunction "2_2") (pintype "passive"))
      (node (ref "C21") (pin "2") (pinfunction "2_2") (pintype "passive"))
      (node (ref "C22") (pin "2") (pinfunction "2_2") (pintype "passive"))
      (node (ref "C23") (pin "2") (pinfunction "2_2") (pintype "passive"))
      (node (ref "C24") (pin "2") (pinfunction "2_2") (pintype "passive"))
      (node (ref "C26") (pin "-") (pinfunction "-_-") (pintype "passive"))
      (node (ref "C3") (pin "2") (pinfunction "2_2") (pintype "passive"))
      (node (ref "C4") (pin "2") (pinfunction "2_2") (pintype "passive"))
      (node (ref "C5") (pin "2") (pinfunction "2_2") (pintype "passive"))
      (node (ref "C6") (pin "2") (pinfunction "2_2") (pintype "passive"))
      (node (ref "C7") (pin "2") (pinfunction "2_2") (pintype "passive"))
      (node (ref "C8") (pin "2") (pinfunction "2_2") (pintype "passive"))
      (node (ref "C9") (pin "2") (pinfunction "2_2") (pintype "passive"))
      (node (ref "R2") (pin "1") (pinfunction "1_1") (pintype "passive"))
      (node (ref "R4") (pin "1") (pinfunction "1_1") (pintype "passive"))
      (node (ref "U$5") (pin "AC2") (pinfunction "1_AC2") (pintype "bidirectional"))
      (node (ref "U$5") (pin "AT1") (pinfunction "1_AT1") (pintype "bidirectional"))
      (node (ref "U$5") (pin "BC2") (pinfunction "1_BC2") (pintype "bidirectional"))
      (node (ref "U$5") (pin "BT1") (pinfunction "1_BT1") (pintype "bidirectional"))
    )
    (net (code "57") (name "Net-(E19A-I9)") (class "Default")
      (node (ref "E19") (pin "12") (pinfunction "I9_12") (pintype "passive"))
      (node (ref "E7") (pin "12") (pinfunction "I5_12") (pintype "passive"))
    )
    (net (code "58") (name "Net-(E19A-I10)") (class "Default")
      (node (ref "E19") (pin "11") (pinfunction "I10_11") (pintype "passive"))
      (node (ref "E7") (pin "11") (pinfunction "I6_11") (pintype "passive"))
    )
    (net (code "59") (name "Net-(E19A-O)") (class "Default")
      (node (ref "E19") (pin "8") (pinfunction "O_8") (pintype "output"))
      (node (ref "E4") (pin "5") (pinfunction "I0_5") (pintype "input"))
      (node (ref "E7") (pin "8") (pinfunction "O_8") (pintype "output"))
    )
    (net (code "60") (name "VCC") (class "Default")
      (node (ref "C1") (pin "1") (pinfunction "1_1") (pintype "passive"))
      (node (ref "C10") (pin "1") (pinfunction "1_1") (pintype "passive"))
      (node (ref "C11") (pin "1") (pinfunction "1_1") (pintype "passive"))
      (node (ref "C12") (pin "1") (pinfunction "1_1") (pintype "passive"))
      (node (ref "C13") (pin "1") (pinfunction "1_1") (pintype "passive"))
      (node (ref "C14") (pin "1") (pinfunction "1_1") (pintype "passive"))
      (node (ref "C15") (pin "1") (pinfunction "1_1") (pintype "passive"))
      (node (ref "C16") (pin "1") (pinfunction "1_1") (pintype "passive"))
      (node (ref "C17") (pin "1") (pinfunction "1_1") (pintype "passive"))
      (node (ref "C18") (pin "1") (pinfunction "1_1") (pintype "passive"))
      (node (ref "C19") (pin "1") (pinfunction "1_1") (pintype "passive"))
      (node (ref "C2") (pin "1") (pinfunction "1_1") (pintype "passive"))
      (node (ref "C20") (pin "1") (pinfunction "1_1") (pintype "passive"))
      (node (ref "C21") (pin "1") (pinfunction "1_1") (pintype "passive"))
      (node (ref "C24") (pin "1") (pinfunction "1_1") (pintype "passive"))
      (node (ref "C26") (pin "+") (pinfunction "+_+") (pintype "passive"))
      (node (ref "C3") (pin "1") (pinfunction "1_1") (pintype "passive"))
      (node (ref "C4") (pin "1") (pinfunction "1_1") (pintype "passive"))
      (node (ref "C5") (pin "1") (pinfunction "1_1") (pintype "passive"))
      (node (ref "C6") (pin "1") (pinfunction "1_1") (pintype "passive"))
      (node (ref "C7") (pin "1") (pinfunction "1_1") (pintype "passive"))
      (node (ref "C8") (pin "1") (pinfunction "1_1") (pintype "passive"))
      (node (ref "C9") (pin "1") (pinfunction "1_1") (pintype "passive"))
      (node (ref "R1") (pin "2") (pinfunction "2_2") (pintype "passive"))
      (node (ref "R3") (pin "2") (pinfunction "2_2") (pintype "passive"))
      (node (ref "U$5") (pin "AA2") (pinfunction "1_AA2") (pintype "bidirectional"))
      (node (ref "U$5") (pin "BA2") (pinfunction "1_BA2") (pintype "bidirectional"))
    )
    (net (code "61") (name "unconnected-(E10A-~{Q}-Pad6)") (class "Default")
      (node (ref "E10") (pin "6") (pinfunction "~{Q}_6") (pintype "output"))
    )
    (net (code "62") (name "unconnected-(E10B-~{Q}-Pad8)") (class "Default")
      (node (ref "E10") (pin "8") (pinfunction "~{Q}_8") (pintype "output"))
    )
    (net (code "63") (name "unconnected-(E13A-~{Q}-Pad6)") (class "Default")
      (node (ref "E13") (pin "6") (pinfunction "~{Q}_6") (pintype "output"))
    )
    (net (code "64") (name "unconnected-(E13B-~{Q}-Pad8)") (class "Default")
      (node (ref "E13") (pin "8") (pinfunction "~{Q}_8") (pintype "output"))
    )
    (net (code "65") (name "unconnected-(E16A-~{Q}-Pad6)") (class "Default")
      (node (ref "E16") (pin "6") (pinfunction "~{Q}_6") (pintype "output"))
    )
    (net (code "66") (name "unconnected-(E16B-~{Q}-Pad8)") (class "Default")
      (node (ref "E16") (pin "8") (pinfunction "~{Q}_8") (pintype "output"))
    )
  )
)
